# charger.net
KiCad netlist of a schematic drawn in EAGLE
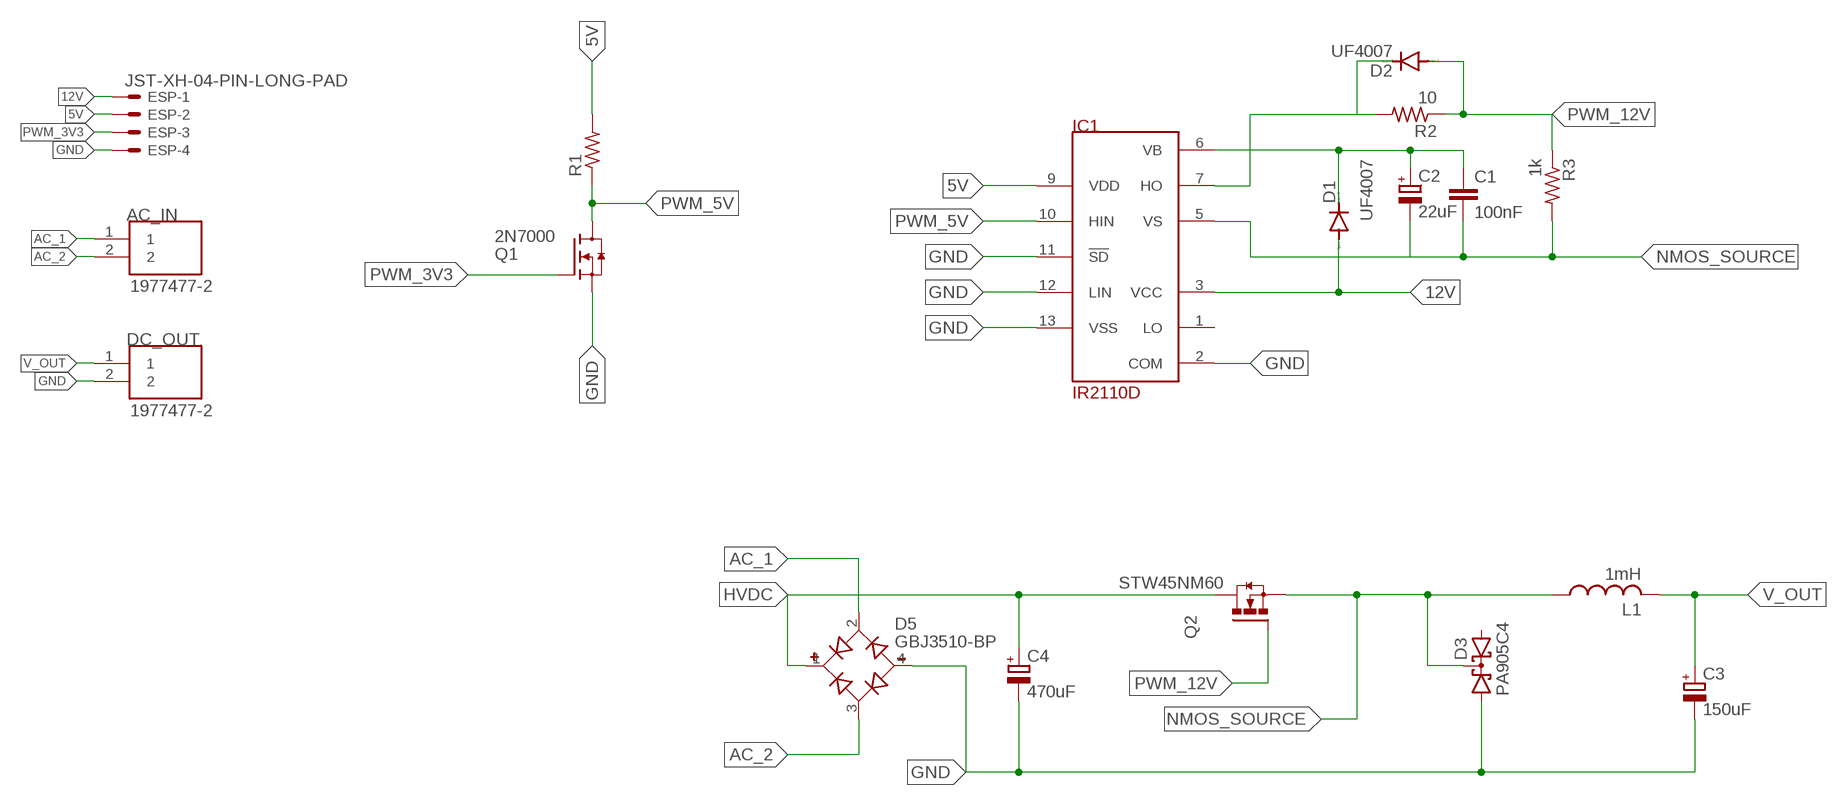
[diagram p0: schematic, sheet 1]

(export (version "E")
  (design (tool "Eeschema 10.0.6"))
  (components
    (comp (ref "AC_IN")
      (value "1977477-2")
      (footprint "eagle-import:TE_1977477-2")
      (fields (field (name "MF") "TE Connectivity"))
      (libsource (lib "eagle-import") (part "1977477-2"))
    )
    (comp (ref "C1")
      (value "100nF")
      (footprint "eagle-import:C025-025X050")
      (libsource (lib "eagle-import") (part "C-EU025-025X050"))
    )
    (comp (ref "C2")
      (value "22uF")
      (footprint "eagle-import:E2,5-6E")
      (libsource (lib "eagle-import") (part "CPOL-EUE2,5-6E"))
    )
    (comp (ref "C3")
      (value "150uF")
      (footprint "eagle-import:E7,5-18")
      (libsource (lib "eagle-import") (part "CPOL-EUE7.5-18"))
    )
    (comp (ref "C4")
      (value "470uF")
      (footprint "eagle-import:EB35D")
      (libsource (lib "eagle-import") (part "CPOL-EUE10-35"))
    )
    (comp (ref "D1")
      (value "UF4007")
      (footprint "eagle-import:DO34-7")
      (libsource (lib "eagle-import") (part "BAS15"))
    )
    (comp (ref "D2")
      (value "UF4007")
      (footprint "eagle-import:DO34-7")
      (libsource (lib "eagle-import") (part "BAS15"))
    )
    (comp (ref "D3")
      (value "PA905C4")
      (footprint "eagle-import:SOT93S")
      (libsource (lib "eagle-import") (part "PBYR3035"))
    )
    (comp (ref "D5")
      (value "GBJ3510-BP")
      (footprint "eagle-import:DIOB_GBJ3510-BP")
      (fields (field (name "MF") "Micro Commercial"))
      (libsource (lib "eagle-import") (part "GBJ3510-BP"))
    )
    (comp (ref "DC_OUT")
      (value "1977477-2")
      (footprint "eagle-import:TE_1977477-2")
      (fields (field (name "MF") "TE Connectivity"))
      (libsource (lib "eagle-import") (part "1977477-2"))
    )
    (comp (ref "ESP")
      (value "JST-XH-04-PIN-LONG-PAD")
      (footprint "eagle-import:JST-XH-04-PACKAGE-LONG-PAD")
      (libsource (lib "eagle-import") (part "JST-XH-04-PIN-LONG-PAD"))
    )
    (comp (ref "IC1")
      (value "IR2110D")
      (footprint "eagle-import:DIL14")
      (libsource (lib "eagle-import") (part "IR2110D"))
    )
    (comp (ref "L1")
      (value "1mH")
      (footprint "eagle-import:TJ7-U1")
      (libsource (lib "eagle-import") (part "L-USTJ7-U1"))
    )
    (comp (ref "Q1")
      (value "2N7000")
      (footprint "eagle-import:TO92")
      (fields (field (name "MF") "STMicroelectronics"))
      (libsource (lib "eagle-import") (part "2N7000"))
    )
    (comp (ref "Q2")
      (value "STW45NM60")
      (footprint "eagle-import:TO247AC")
      (fields (field (name "MF") "Vishay Siliconix") (field (name "MP") "IRFP240"))
      (libsource (lib "eagle-import") (part "IRFP240"))
    )
    (comp (ref "R1")
      (value "R-US_0204/7")
      (footprint "eagle-import:0204_7")
      (libsource (lib "eagle-import") (part "R-US_0204/7"))
    )
    (comp (ref "R2")
      (value "10")
      (footprint "eagle-import:0204_7")
      (libsource (lib "eagle-import") (part "R-US_0204/7"))
    )
    (comp (ref "R3")
      (value "1k")
      (footprint "eagle-import:0204_7")
      (libsource (lib "eagle-import") (part "R-US_0204/7"))
    )
  )
  (nets
    (net (code "1") (name "5V") (class "Default")
      (node (ref "ESP") (pin "2") (pinfunction "S_2") (pintype "passive"))
      (node (ref "IC1") (pin "9") (pinfunction "VDD_9") (pintype "power_in"))
      (node (ref "R1") (pin "2") (pinfunction "2_2") (pintype "passive"))
    )
    (net (code "2") (name "12V") (class "Default")
      (node (ref "D1") (pin "A") (pinfunction "A_A") (pintype "passive"))
      (node (ref "ESP") (pin "1") (pinfunction "S_1") (pintype "passive"))
      (node (ref "IC1") (pin "3") (pinfunction "VCC_3") (pintype "power_in"))
    )
    (net (code "3") (name "AC_1") (class "Default")
      (node (ref "AC_IN") (pin "1") (pinfunction "1_1") (pintype "passive"))
      (node (ref "D5") (pin "2") (pinfunction "AC1_2") (pintype "passive"))
    )
    (net (code "4") (name "AC_2") (class "Default")
      (node (ref "AC_IN") (pin "2") (pinfunction "2_2") (pintype "passive"))
      (node (ref "D5") (pin "3") (pinfunction "AC2_3") (pintype "passive"))
    )
    (net (code "5") (name "GND") (class "Default")
      (node (ref "C3") (pin "-") (pinfunction "-_-") (pintype "passive"))
      (node (ref "C4") (pin "-") (pinfunction "-_-") (pintype "passive"))
      (node (ref "D3") (pin "A1") (pinfunction "A1_A1") (pintype "passive"))
      (node (ref "D5") (pin "4") (pinfunction "-_4") (pintype "passive"))
      (node (ref "DC_OUT") (pin "2") (pinfunction "2_2") (pintype "passive"))
      (node (ref "ESP") (pin "4") (pinfunction "S_4") (pintype "passive"))
      (node (ref "IC1") (pin "11") (pinfunction "~{SD}_11") (pintype "input"))
      (node (ref "IC1") (pin "12") (pinfunction "LIN_12") (pintype "input"))
      (node (ref "IC1") (pin "13") (pinfunction "VSS_13") (pintype "power_in"))
      (node (ref "IC1") (pin "2") (pinfunction "COM_2") (pintype "power_in"))
      (node (ref "Q1") (pin "1") (pinfunction "S_1") (pintype "passive"))
    )
    (net (code "6") (name "HVDC") (class "Default")
      (node (ref "C4") (pin "+") (pinfunction "+_+") (pintype "passive"))
      (node (ref "D5") (pin "1") (pinfunction "+_1") (pintype "passive"))
      (node (ref "Q2") (pin "2") (pinfunction "D_2") (pintype "passive"))
    )
    (net (code "7") (name "NMOS_SOURCE") (class "Default")
      (node (ref "C1") (pin "2") (pinfunction "2_2") (pintype "passive"))
      (node (ref "C2") (pin "-") (pinfunction "-_-") (pintype "passive"))
      (node (ref "D3") (pin "C") (pinfunction "C_C") (pintype "passive"))
      (node (ref "IC1") (pin "5") (pinfunction "VS_5") (pintype "power_in"))
      (node (ref "L1") (pin "1") (pinfunction "1_1") (pintype "passive"))
      (node (ref "Q2") (pin "3") (pinfunction "S_3") (pintype "passive"))
      (node (ref "R3") (pin "2") (pinfunction "2_2") (pintype "passive"))
    )
    (net (code "8") (name "Net-(IC1-HO)") (class "Default")
      (node (ref "D2") (pin "C") (pinfunction "C_C") (pintype "passive"))
      (node (ref "IC1") (pin "7") (pinfunction "HO_7") (pintype "output"))
      (node (ref "R2") (pin "2") (pinfunction "2_2") (pintype "passive"))
    )
    (net (code "9") (name "Net-(IC1-VB)") (class "Default")
      (node (ref "C1") (pin "1") (pinfunction "1_1") (pintype "passive"))
      (node (ref "C2") (pin "+") (pinfunction "+_+") (pintype "passive"))
      (node (ref "D1") (pin "C") (pinfunction "C_C") (pintype "passive"))
      (node (ref "IC1") (pin "6") (pinfunction "VB_6") (pintype "power_in"))
    )
    (net (code "10") (name "PWM_3V3") (class "Default")
      (node (ref "ESP") (pin "3") (pinfunction "S_3") (pintype "passive"))
      (node (ref "Q1") (pin "2") (pinfunction "G_2") (pintype "passive"))
    )
    (net (code "11") (name "PWM_5V") (class "Default")
      (node (ref "IC1") (pin "10") (pinfunction "HIN_10") (pintype "input"))
      (node (ref "Q1") (pin "3") (pinfunction "D_3") (pintype "passive"))
      (node (ref "R1") (pin "1") (pinfunction "1_1") (pintype "passive"))
    )
    (net (code "12") (name "PWM_12V") (class "Default")
      (node (ref "D2") (pin "A") (pinfunction "A_A") (pintype "passive"))
      (node (ref "Q2") (pin "1") (pinfunction "G_1") (pintype "passive"))
      (node (ref "R2") (pin "1") (pinfunction "1_1") (pintype "passive"))
      (node (ref "R3") (pin "1") (pinfunction "1_1") (pintype "passive"))
    )
    (net (code "13") (name "V_OUT") (class "Default")
      (node (ref "C3") (pin "+") (pinfunction "+_+") (pintype "passive"))
      (node (ref "DC_OUT") (pin "1") (pinfunction "1_1") (pintype "passive"))
      (node (ref "L1") (pin "2") (pinfunction "2_2") (pintype "passive"))
    )
    (net (code "14") (name "unconnected-(D3-PadA2)") (class "Default")
      (node (ref "D3") (pin "A2") (pinfunction "A2_A2") (pintype "passive"))
    )
    (net (code "15") (name "unconnected-(IC1-LO-Pad1)") (class "Default")
      (node (ref "IC1") (pin "1") (pinfunction "LO_1") (pintype "output"))
    )
  )
)
